# untitled.net
KiCad netlist of a schematic drawn in EAGLE
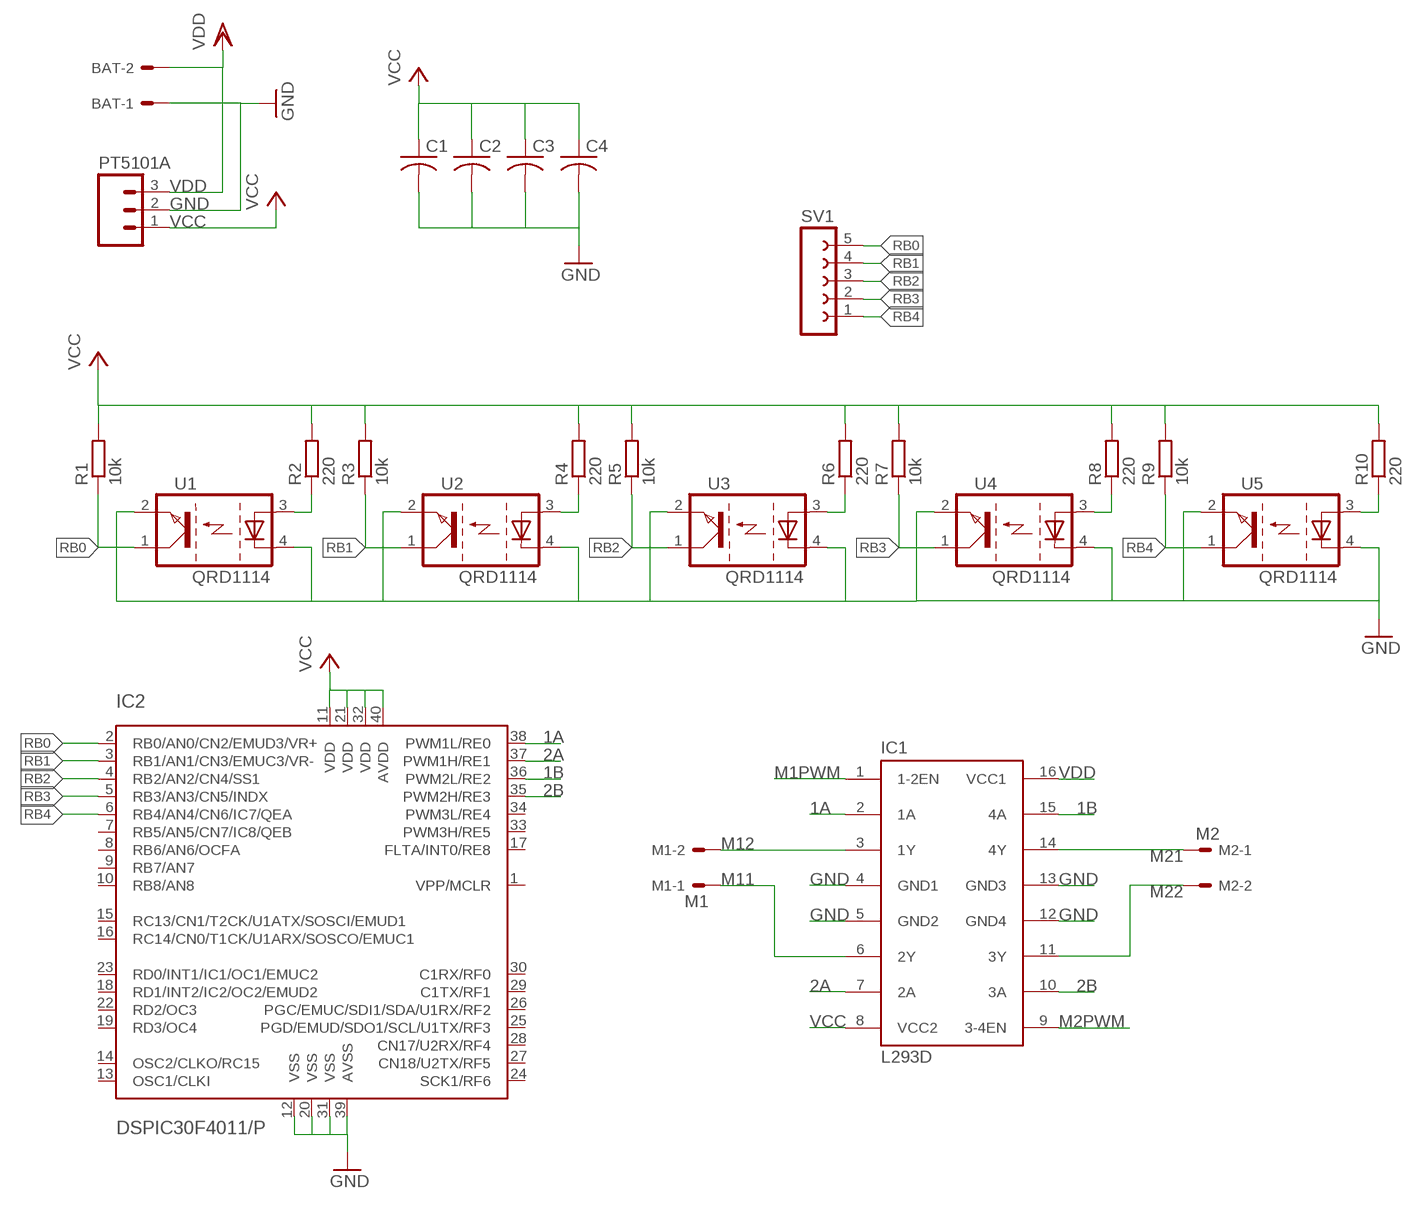
[diagram p0: schematic, sheet 1]

(export (version "E")
  (design (tool "Eeschema 10.0.6"))
  (components
    (comp (ref "BAT")
      (value "22-27-2021-02")
      (footprint "eagle-import:6410-02")
      (libsource (lib "eagle-import") (part "22-?-0227-2021"))
    )
    (comp (ref "C1")
      (value "C-US025-024X044")
      (footprint "eagle-import:C025-024X044")
      (libsource (lib "eagle-import") (part "C-US025-024X044"))
    )
    (comp (ref "C2")
      (value "C-US025-024X044")
      (footprint "eagle-import:C025-024X044")
      (libsource (lib "eagle-import") (part "C-US025-024X044"))
    )
    (comp (ref "C3")
      (value "C-US025-024X044")
      (footprint "eagle-import:C025-024X044")
      (libsource (lib "eagle-import") (part "C-US025-024X044"))
    )
    (comp (ref "C4")
      (value "C-US025-024X044")
      (footprint "eagle-import:C025-024X044")
      (libsource (lib "eagle-import") (part "C-US025-024X044"))
    )
    (comp (ref "IC1")
      (value "L293D")
      (footprint "eagle-import:DIL16")
      (libsource (lib "eagle-import") (part "L293D"))
    )
    (comp (ref "IC2")
      (value "DSPIC30F4011/P")
      (footprint "eagle-import:DIL40")
      (libsource (lib "eagle-import") (part "DSPIC30F4011/P"))
    )
    (comp (ref "M1")
      (value "M1")
      (footprint "eagle-import:6410-02")
      (libsource (lib "eagle-import") (part "22-?-0227-2021"))
    )
    (comp (ref "M2")
      (value "M2")
      (footprint "eagle-import:6410-02")
      (libsource (lib "eagle-import") (part "22-?-0227-2021"))
    )
    (comp (ref "PT5101A")
      (value "M03")
      (footprint "eagle-import:03P")
      (libsource (lib "eagle-import") (part "M03"))
    )
    (comp (ref "R1")
      (value "10k")
      (footprint "eagle-import:0204_5")
      (libsource (lib "eagle-import") (part "R-EU_0204/5"))
    )
    (comp (ref "R2")
      (value "220")
      (footprint "eagle-import:0204_5")
      (libsource (lib "eagle-import") (part "R-EU_0204/5"))
    )
    (comp (ref "R3")
      (value "10k")
      (footprint "eagle-import:0204_5")
      (libsource (lib "eagle-import") (part "R-EU_0204/5"))
    )
    (comp (ref "R4")
      (value "220")
      (footprint "eagle-import:0204_5")
      (libsource (lib "eagle-import") (part "R-EU_0204/5"))
    )
    (comp (ref "R5")
      (value "10k")
      (footprint "eagle-import:0204_5")
      (libsource (lib "eagle-import") (part "R-EU_0204/5"))
    )
    (comp (ref "R6")
      (value "220")
      (footprint "eagle-import:0204_5")
      (libsource (lib "eagle-import") (part "R-EU_0204/5"))
    )
    (comp (ref "R7")
      (value "10k")
      (footprint "eagle-import:0204_5")
      (libsource (lib "eagle-import") (part "R-EU_0204/5"))
    )
    (comp (ref "R8")
      (value "220")
      (footprint "eagle-import:0204_5")
      (libsource (lib "eagle-import") (part "R-EU_0204/5"))
    )
    (comp (ref "R9")
      (value "10k")
      (footprint "eagle-import:0204_5")
      (libsource (lib "eagle-import") (part "R-EU_0204/5"))
    )
    (comp (ref "R10")
      (value "220")
      (footprint "eagle-import:0204_5")
      (libsource (lib "eagle-import") (part "R-EU_0204/5"))
    )
    (comp (ref "SV1")
      (value "FE05-1")
      (footprint "eagle-import:FE05-1")
      (libsource (lib "eagle-import") (part "FE05-1"))
    )
    (comp (ref "U1")
      (value "QRD1114")
      (footprint "eagle-import:QRD1114")
      (libsource (lib "eagle-import") (part "QRD1114"))
    )
    (comp (ref "U2")
      (value "QRD1114")
      (footprint "eagle-import:QRD1114")
      (libsource (lib "eagle-import") (part "QRD1114"))
    )
    (comp (ref "U3")
      (value "QRD1114")
      (footprint "eagle-import:QRD1114")
      (libsource (lib "eagle-import") (part "QRD1114"))
    )
    (comp (ref "U4")
      (value "QRD1114")
      (footprint "eagle-import:QRD1114")
      (libsource (lib "eagle-import") (part "QRD1114"))
    )
    (comp (ref "U5")
      (value "QRD1114")
      (footprint "eagle-import:QRD1114")
      (libsource (lib "eagle-import") (part "QRD1114"))
    )
  )
  (nets
    (net (code "1") (name "/1A") (class "Default")
      (node (ref "IC1") (pin "2") (pinfunction "1A_2") (pintype "input"))
      (node (ref "IC2") (pin "38") (pinfunction "PWM1L/RE0_38") (pintype "bidirectional"))
    )
    (net (code "2") (name "/1B") (class "Default")
      (node (ref "IC1") (pin "15") (pinfunction "4A_15") (pintype "input"))
      (node (ref "IC2") (pin "36") (pinfunction "PWM2L/RE2_36") (pintype "bidirectional"))
    )
    (net (code "3") (name "/2A") (class "Default")
      (node (ref "IC1") (pin "7") (pinfunction "2A_7") (pintype "input"))
      (node (ref "IC2") (pin "37") (pinfunction "PWM1H/RE1_37") (pintype "bidirectional"))
    )
    (net (code "4") (name "/2B") (class "Default")
      (node (ref "IC1") (pin "10") (pinfunction "3A_10") (pintype "input"))
      (node (ref "IC2") (pin "35") (pinfunction "PWM2H/RE3_35") (pintype "bidirectional"))
    )
    (net (code "5") (name "/M1PWM") (class "Default")
      (node (ref "IC1") (pin "1") (pinfunction "1-2EN_1") (pintype "input"))
    )
    (net (code "6") (name "/M2PWM") (class "Default")
      (node (ref "IC1") (pin "9") (pinfunction "3-4EN_9") (pintype "input"))
    )
    (net (code "7") (name "/M11") (class "Default")
      (node (ref "IC1") (pin "6") (pinfunction "2Y_6") (pintype "output"))
      (node (ref "M1") (pin "1") (pinfunction "S_1") (pintype "passive"))
    )
    (net (code "8") (name "/M12") (class "Default")
      (node (ref "IC1") (pin "3") (pinfunction "1Y_3") (pintype "output"))
      (node (ref "M1") (pin "2") (pinfunction "S_2") (pintype "passive"))
    )
    (net (code "9") (name "/M21") (class "Default")
      (node (ref "IC1") (pin "14") (pinfunction "4Y_14") (pintype "output"))
      (node (ref "M2") (pin "1") (pinfunction "S_1") (pintype "passive"))
    )
    (net (code "10") (name "/M22") (class "Default")
      (node (ref "IC1") (pin "11") (pinfunction "3Y_11") (pintype "output"))
      (node (ref "M2") (pin "2") (pinfunction "S_2") (pintype "passive"))
    )
    (net (code "11") (name "GND") (class "Default")
      (node (ref "BAT") (pin "1") (pinfunction "S_1") (pintype "passive"))
      (node (ref "C1") (pin "2") (pinfunction "2_2") (pintype "passive"))
      (node (ref "C2") (pin "2") (pinfunction "2_2") (pintype "passive"))
      (node (ref "C3") (pin "2") (pinfunction "2_2") (pintype "passive"))
      (node (ref "C4") (pin "2") (pinfunction "2_2") (pintype "passive"))
      (node (ref "IC1") (pin "12") (pinfunction "GND4_12") (pintype "power_in"))
      (node (ref "IC1") (pin "13") (pinfunction "GND3_13") (pintype "power_in"))
      (node (ref "IC1") (pin "4") (pinfunction "GND1_4") (pintype "power_in"))
      (node (ref "IC1") (pin "5") (pinfunction "GND2_5") (pintype "power_in"))
      (node (ref "IC2") (pin "12") (pinfunction "VSS_12") (pintype "power_in"))
      (node (ref "IC2") (pin "20") (pinfunction "VSS_20") (pintype "power_in"))
      (node (ref "IC2") (pin "31") (pinfunction "VSS_31") (pintype "power_in"))
      (node (ref "IC2") (pin "39") (pinfunction "AVSS_39") (pintype "power_in"))
      (node (ref "PT5101A") (pin "2") (pinfunction "2_2") (pintype "passive"))
      (node (ref "U1") (pin "2") (pinfunction "2_2") (pintype "passive"))
      (node (ref "U1") (pin "4") (pinfunction "4_4") (pintype "passive"))
      (node (ref "U2") (pin "2") (pinfunction "2_2") (pintype "passive"))
      (node (ref "U2") (pin "4") (pinfunction "4_4") (pintype "passive"))
      (node (ref "U3") (pin "2") (pinfunction "2_2") (pintype "passive"))
      (node (ref "U3") (pin "4") (pinfunction "4_4") (pintype "passive"))
      (node (ref "U4") (pin "2") (pinfunction "2_2") (pintype "passive"))
      (node (ref "U4") (pin "4") (pinfunction "4_4") (pintype "passive"))
      (node (ref "U5") (pin "2") (pinfunction "2_2") (pintype "passive"))
      (node (ref "U5") (pin "4") (pinfunction "4_4") (pintype "passive"))
    )
    (net (code "12") (name "Net-(R2-Pad1)") (class "Default")
      (node (ref "R2") (pin "1") (pinfunction "1_1") (pintype "passive"))
      (node (ref "U1") (pin "3") (pinfunction "3_3") (pintype "passive"))
    )
    (net (code "13") (name "Net-(R4-Pad1)") (class "Default")
      (node (ref "R4") (pin "1") (pinfunction "1_1") (pintype "passive"))
      (node (ref "U2") (pin "3") (pinfunction "3_3") (pintype "passive"))
    )
    (net (code "14") (name "Net-(R6-Pad1)") (class "Default")
      (node (ref "R6") (pin "1") (pinfunction "1_1") (pintype "passive"))
      (node (ref "U3") (pin "3") (pinfunction "3_3") (pintype "passive"))
    )
    (net (code "15") (name "Net-(R8-Pad1)") (class "Default")
      (node (ref "R8") (pin "1") (pinfunction "1_1") (pintype "passive"))
      (node (ref "U4") (pin "3") (pinfunction "3_3") (pintype "passive"))
    )
    (net (code "16") (name "Net-(R10-Pad1)") (class "Default")
      (node (ref "R10") (pin "1") (pinfunction "1_1") (pintype "passive"))
      (node (ref "U5") (pin "3") (pinfunction "3_3") (pintype "passive"))
    )
    (net (code "17") (name "RB0") (class "Default")
      (node (ref "IC2") (pin "2") (pinfunction "RB0/AN0/CN2/EMUD3/VR+_2") (pintype "bidirectional"))
      (node (ref "R1") (pin "1") (pinfunction "1_1") (pintype "passive"))
      (node (ref "SV1") (pin "5") (pinfunction "5_5") (pintype "passive"))
      (node (ref "U1") (pin "1") (pinfunction "1_1") (pintype "passive"))
    )
    (net (code "18") (name "RB1") (class "Default")
      (node (ref "IC2") (pin "3") (pinfunction "RB1/AN1/CN3/EMUC3/VR-_3") (pintype "bidirectional"))
      (node (ref "R3") (pin "1") (pinfunction "1_1") (pintype "passive"))
      (node (ref "SV1") (pin "4") (pinfunction "4_4") (pintype "passive"))
      (node (ref "U2") (pin "1") (pinfunction "1_1") (pintype "passive"))
    )
    (net (code "19") (name "RB2") (class "Default")
      (node (ref "IC2") (pin "4") (pinfunction "RB2/AN2/CN4/SS1_4") (pintype "bidirectional"))
      (node (ref "R5") (pin "1") (pinfunction "1_1") (pintype "passive"))
      (node (ref "SV1") (pin "3") (pinfunction "3_3") (pintype "passive"))
      (node (ref "U3") (pin "1") (pinfunction "1_1") (pintype "passive"))
    )
    (net (code "20") (name "RB3") (class "Default")
      (node (ref "IC2") (pin "5") (pinfunction "RB3/AN3/CN5/INDX_5") (pintype "bidirectional"))
      (node (ref "R7") (pin "1") (pinfunction "1_1") (pintype "passive"))
      (node (ref "SV1") (pin "2") (pinfunction "2_2") (pintype "passive"))
      (node (ref "U4") (pin "1") (pinfunction "1_1") (pintype "passive"))
    )
    (net (code "21") (name "RB4") (class "Default")
      (node (ref "IC2") (pin "6") (pinfunction "RB4/AN4/CN6/IC7/QEA_6") (pintype "bidirectional"))
      (node (ref "R9") (pin "1") (pinfunction "1_1") (pintype "passive"))
      (node (ref "SV1") (pin "1") (pinfunction "1_1") (pintype "passive"))
      (node (ref "U5") (pin "1") (pinfunction "1_1") (pintype "passive"))
    )
    (net (code "22") (name "VCC") (class "Default")
      (node (ref "C1") (pin "1") (pinfunction "1_1") (pintype "passive"))
      (node (ref "C2") (pin "1") (pinfunction "1_1") (pintype "passive"))
      (node (ref "C3") (pin "1") (pinfunction "1_1") (pintype "passive"))
      (node (ref "C4") (pin "1") (pinfunction "1_1") (pintype "passive"))
      (node (ref "IC1") (pin "8") (pinfunction "VCC2_8") (pintype "power_in"))
      (node (ref "IC2") (pin "11") (pinfunction "VDD_11") (pintype "power_in"))
      (node (ref "IC2") (pin "21") (pinfunction "VDD_21") (pintype "power_in"))
      (node (ref "IC2") (pin "32") (pinfunction "VDD_32") (pintype "power_in"))
      (node (ref "IC2") (pin "40") (pinfunction "AVDD_40") (pintype "power_in"))
      (node (ref "PT5101A") (pin "1") (pinfunction "1_1") (pintype "passive"))
      (node (ref "R1") (pin "2") (pinfunction "2_2") (pintype "passive"))
      (node (ref "R10") (pin "2") (pinfunction "2_2") (pintype "passive"))
      (node (ref "R2") (pin "2") (pinfunction "2_2") (pintype "passive"))
      (node (ref "R3") (pin "2") (pinfunction "2_2") (pintype "passive"))
      (node (ref "R4") (pin "2") (pinfunction "2_2") (pintype "passive"))
      (node (ref "R5") (pin "2") (pinfunction "2_2") (pintype "passive"))
      (node (ref "R6") (pin "2") (pinfunction "2_2") (pintype "passive"))
      (node (ref "R7") (pin "2") (pinfunction "2_2") (pintype "passive"))
      (node (ref "R8") (pin "2") (pinfunction "2_2") (pintype "passive"))
      (node (ref "R9") (pin "2") (pinfunction "2_2") (pintype "passive"))
    )
    (net (code "23") (name "VDD") (class "Default")
      (node (ref "BAT") (pin "2") (pinfunction "S_2") (pintype "passive"))
      (node (ref "IC1") (pin "16") (pinfunction "VCC1_16") (pintype "power_in"))
      (node (ref "PT5101A") (pin "3") (pinfunction "3_3") (pintype "passive"))
    )
    (net (code "24") (name "unconnected-(IC2-C1RX{slash}RF0-Pad30)") (class "Default")
      (node (ref "IC2") (pin "30") (pinfunction "C1RX/RF0_30") (pintype "bidirectional"))
    )
    (net (code "25") (name "unconnected-(IC2-C1TX{slash}RF1-Pad29)") (class "Default")
      (node (ref "IC2") (pin "29") (pinfunction "C1TX/RF1_29") (pintype "bidirectional"))
    )
    (net (code "26") (name "unconnected-(IC2-CN17{slash}U2RX{slash}RF4-Pad28)") (class "Default")
      (node (ref "IC2") (pin "28") (pinfunction "CN17/U2RX/RF4_28") (pintype "bidirectional"))
    )
    (net (code "27") (name "unconnected-(IC2-CN18{slash}U2TX{slash}RF5-Pad27)") (class "Default")
      (node (ref "IC2") (pin "27") (pinfunction "CN18/U2TX/RF5_27") (pintype "bidirectional"))
    )
    (net (code "28") (name "unconnected-(IC2-FLTA{slash}INT0{slash}RE8-Pad17)") (class "Default")
      (node (ref "IC2") (pin "17") (pinfunction "FLTA/INT0/RE8_17") (pintype "bidirectional"))
    )
    (net (code "29") (name "unconnected-(IC2-OSC1{slash}CLKI-Pad13)") (class "Default")
      (node (ref "IC2") (pin "13") (pinfunction "OSC1/CLKI_13") (pintype "input"))
    )
    (net (code "30") (name "unconnected-(IC2-OSC2{slash}CLKO{slash}RC15-Pad14)") (class "Default")
      (node (ref "IC2") (pin "14") (pinfunction "OSC2/CLKO/RC15_14") (pintype "bidirectional"))
    )
    (net (code "31") (name "unconnected-(IC2-PGC{slash}EMUC{slash}SDI1{slash}SDA{slash}U1RX{slash}RF2-Pad26)") (class "Default")
      (node (ref "IC2") (pin "26") (pinfunction "PGC/EMUC/SDI1/SDA/U1RX/RF2_26") (pintype "bidirectional"))
    )
    (net (code "32") (name "unconnected-(IC2-PGD{slash}EMUD{slash}SDO1{slash}SCL{slash}U1TX{slash}RF3-Pad25)") (class "Default")
      (node (ref "IC2") (pin "25") (pinfunction "PGD/EMUD/SDO1/SCL/U1TX/RF3_25") (pintype "bidirectional"))
    )
    (net (code "33") (name "unconnected-(IC2-PWM3H{slash}RE5-Pad33)") (class "Default")
      (node (ref "IC2") (pin "33") (pinfunction "PWM3H/RE5_33") (pintype "bidirectional"))
    )
    (net (code "34") (name "unconnected-(IC2-PWM3L{slash}RE4-Pad34)") (class "Default")
      (node (ref "IC2") (pin "34") (pinfunction "PWM3L/RE4_34") (pintype "bidirectional"))
    )
    (net (code "35") (name "unconnected-(IC2-RB5{slash}AN5{slash}CN7{slash}IC8{slash}QEB-Pad7)") (class "Default")
      (node (ref "IC2") (pin "7") (pinfunction "RB5/AN5/CN7/IC8/QEB_7") (pintype "bidirectional"))
    )
    (net (code "36") (name "unconnected-(IC2-RB6{slash}AN6{slash}OCFA-Pad8)") (class "Default")
      (node (ref "IC2") (pin "8") (pinfunction "RB6/AN6/OCFA_8") (pintype "bidirectional"))
    )
    (net (code "37") (name "unconnected-(IC2-RB7{slash}AN7-Pad9)") (class "Default")
      (node (ref "IC2") (pin "9") (pinfunction "RB7/AN7_9") (pintype "bidirectional"))
    )
    (net (code "38") (name "unconnected-(IC2-RB8{slash}AN8-Pad10)") (class "Default")
      (node (ref "IC2") (pin "10") (pinfunction "RB8/AN8_10") (pintype "bidirectional"))
    )
    (net (code "39") (name "unconnected-(IC2-RC13{slash}CN1{slash}T2CK{slash}U1ATX{slash}SOSCI{slash}EMUD1-Pad15)") (class "Default")
      (node (ref "IC2") (pin "15") (pinfunction "RC13/CN1/T2CK/U1ATX/SOSCI/EMUD1_15") (pintype "bidirectional"))
    )
    (net (code "40") (name "unconnected-(IC2-RC14{slash}CN0{slash}T1CK{slash}U1ARX{slash}SOSCO{slash}EMUC1-Pad16)") (class "Default")
      (node (ref "IC2") (pin "16") (pinfunction "RC14/CN0/T1CK/U1ARX/SOSCO/EMUC1_16") (pintype "bidirectional"))
    )
    (net (code "41") (name "unconnected-(IC2-RD0{slash}INT1{slash}IC1{slash}OC1{slash}EMUC2-Pad23)") (class "Default")
      (node (ref "IC2") (pin "23") (pinfunction "RD0/INT1/IC1/OC1/EMUC2_23") (pintype "bidirectional"))
    )
    (net (code "42") (name "unconnected-(IC2-RD1{slash}INT2{slash}IC2{slash}OC2{slash}EMUD2-Pad18)") (class "Default")
      (node (ref "IC2") (pin "18") (pinfunction "RD1/INT2/IC2/OC2/EMUD2_18") (pintype "bidirectional"))
    )
    (net (code "43") (name "unconnected-(IC2-RD2{slash}OC3-Pad22)") (class "Default")
      (node (ref "IC2") (pin "22") (pinfunction "RD2/OC3_22") (pintype "bidirectional"))
    )
    (net (code "44") (name "unconnected-(IC2-RD3{slash}OC4-Pad19)") (class "Default")
      (node (ref "IC2") (pin "19") (pinfunction "RD3/OC4_19") (pintype "bidirectional"))
    )
    (net (code "45") (name "unconnected-(IC2-SCK1{slash}RF6-Pad24)") (class "Default")
      (node (ref "IC2") (pin "24") (pinfunction "SCK1/RF6_24") (pintype "bidirectional"))
    )
    (net (code "46") (name "unconnected-(IC2-VPP{slash}MCLR-Pad1)") (class "Default")
      (node (ref "IC2") (pin "1") (pinfunction "VPP/MCLR_1") (pintype "input"))
    )
  )
)
